# transistor-test-v3.net
KiCad netlist of a schematic drawn in EAGLE
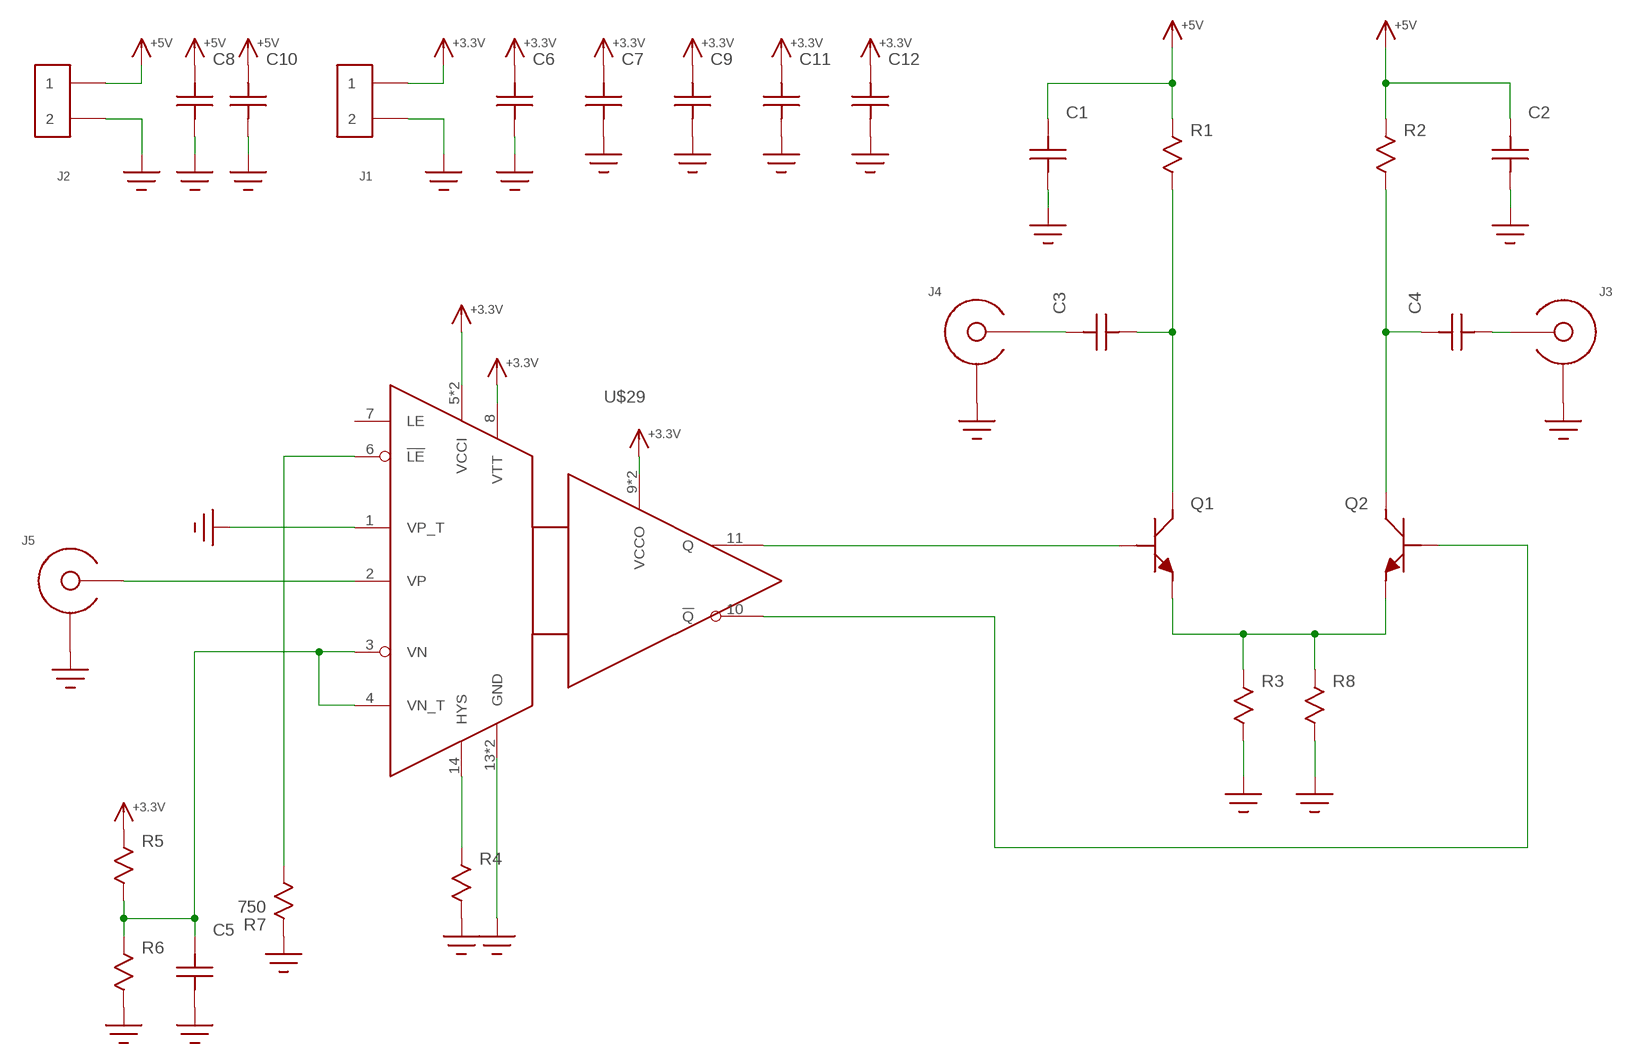
[diagram p0: schematic, sheet 1]

(export (version "E")
  (design (tool "Eeschema 10.0.6"))
  (components
    (comp (ref "C1")
      (value "C0603")
      (footprint "eagle-import:C0603")
      (libsource (lib "eagle-import") (part "C0603"))
    )
    (comp (ref "C2")
      (value "C0603")
      (footprint "eagle-import:C0603")
      (libsource (lib "eagle-import") (part "C0603"))
    )
    (comp (ref "C3")
      (value "C0603")
      (footprint "eagle-import:C0603")
      (libsource (lib "eagle-import") (part "C0603"))
    )
    (comp (ref "C4")
      (value "C0603")
      (footprint "eagle-import:C0603")
      (libsource (lib "eagle-import") (part "C0603"))
    )
    (comp (ref "C5")
      (value "C0603")
      (footprint "eagle-import:C0603")
      (libsource (lib "eagle-import") (part "C0603"))
    )
    (comp (ref "C6")
      (value "C1206")
      (footprint "eagle-import:1206")
      (libsource (lib "eagle-import") (part "C1206"))
    )
    (comp (ref "C7")
      (value "C0603")
      (footprint "eagle-import:C0603")
      (libsource (lib "eagle-import") (part "C0603"))
    )
    (comp (ref "C8")
      (value "C1206")
      (footprint "eagle-import:1206")
      (libsource (lib "eagle-import") (part "C1206"))
    )
    (comp (ref "C9")
      (value "C0603")
      (footprint "eagle-import:C0603")
      (libsource (lib "eagle-import") (part "C0603"))
    )
    (comp (ref "C10")
      (value "C1206")
      (footprint "eagle-import:1206")
      (libsource (lib "eagle-import") (part "C1206"))
    )
    (comp (ref "C11")
      (value "C0603")
      (footprint "eagle-import:C0603")
      (libsource (lib "eagle-import") (part "C0603"))
    )
    (comp (ref "C12")
      (value "C0603")
      (footprint "eagle-import:C0603")
      (libsource (lib "eagle-import") (part "C0603"))
    )
    (comp (ref "J1")
      (value "HEADER_2PIN")
      (footprint "eagle-import:HEADER_2PIN")
      (libsource (lib "eagle-import") (part "HEADER_2PIN"))
    )
    (comp (ref "J2")
      (value "HEADER_2PIN")
      (footprint "eagle-import:HEADER_2PIN")
      (libsource (lib "eagle-import") (part "HEADER_2PIN"))
    )
    (comp (ref "J3")
      (value "SMA-EDGE-LAUNCH4L_4030_TAPER")
      (footprint "eagle-import:SMA_EDGE_LAUNCH_4L_4030_TAPER")
      (libsource (lib "eagle-import") (part "SMA-EDGE-LAUNCH4L_4030_TAPER"))
    )
    (comp (ref "J4")
      (value "SMA-EDGE-LAUNCH4L_4030_TAPER")
      (footprint "eagle-import:SMA_EDGE_LAUNCH_4L_4030_TAPER")
      (libsource (lib "eagle-import") (part "SMA-EDGE-LAUNCH4L_4030_TAPER"))
    )
    (comp (ref "J5")
      (value "SMA-EDGE-LAUNCH4L_4030_TAPER")
      (footprint "eagle-import:SMA_EDGE_LAUNCH_4L_4030_TAPER")
      (libsource (lib "eagle-import") (part "SMA-EDGE-LAUNCH4L_4030_TAPER"))
    )
    (comp (ref "Q1")
      (value "MCH4020")
      (footprint "eagle-import:SOT343")
      (libsource (lib "eagle-import") (part "MCH4020"))
    )
    (comp (ref "Q2")
      (value "MCH4020")
      (footprint "eagle-import:SOT343")
      (libsource (lib "eagle-import") (part "MCH4020"))
    )
    (comp (ref "R1")
      (value "R0603")
      (footprint "eagle-import:R0603")
      (libsource (lib "eagle-import") (part "R0603"))
    )
    (comp (ref "R2")
      (value "R0603")
      (footprint "eagle-import:R0603")
      (libsource (lib "eagle-import") (part "R0603"))
    )
    (comp (ref "R3")
      (value "R0603")
      (footprint "eagle-import:R0603")
      (libsource (lib "eagle-import") (part "R0603"))
    )
    (comp (ref "R4")
      (value "R0603")
      (footprint "eagle-import:R0603")
      (libsource (lib "eagle-import") (part "R0603"))
    )
    (comp (ref "R5")
      (value "R0603")
      (footprint "eagle-import:R0603")
      (libsource (lib "eagle-import") (part "R0603"))
    )
    (comp (ref "R6")
      (value "R0603")
      (footprint "eagle-import:R0603")
      (libsource (lib "eagle-import") (part "R0603"))
    )
    (comp (ref "R7")
      (value "750")
      (footprint "eagle-import:R0603")
      (libsource (lib "eagle-import") (part "R0603"))
    )
    (comp (ref "R8")
      (value "R0603")
      (footprint "eagle-import:R0603")
      (libsource (lib "eagle-import") (part "R0603"))
    )
    (comp (ref "U$29")
      (value "ADCMP572")
      (footprint "eagle-import:TQFN16-EP")
      (libsource (lib "eagle-import") (part "ADCMP572"))
    )
  )
  (nets
    (net (code "1") (name "+3.3V") (class "Default")
      (node (ref "C11") (pin "P$2") (pinfunction "P$2_P$2") (pintype "bidirectional"))
      (node (ref "C12") (pin "P$2") (pinfunction "P$2_P$2") (pintype "bidirectional"))
      (node (ref "C6") (pin "P$2") (pinfunction "P$2_P$2") (pintype "bidirectional"))
      (node (ref "C7") (pin "P$2") (pinfunction "P$2_P$2") (pintype "bidirectional"))
      (node (ref "C9") (pin "P$2") (pinfunction "P$2_P$2") (pintype "bidirectional"))
      (node (ref "J1") (pin "1") (pinfunction "1_1") (pintype "bidirectional"))
      (node (ref "R5") (pin "P$1") (pinfunction "P$3_P$1") (pintype "bidirectional"))
      (node (ref "U$29") (pin "12") (pinfunction "VCCO_12") (pintype "bidirectional"))
      (node (ref "U$29") (pin "16") (pinfunction "VCCI_16") (pintype "bidirectional"))
      (node (ref "U$29") (pin "5") (pinfunction "VCCI_5") (pintype "bidirectional"))
      (node (ref "U$29") (pin "8") (pinfunction "VTT_8") (pintype "bidirectional"))
      (node (ref "U$29") (pin "9") (pinfunction "VCCO_9") (pintype "bidirectional"))
    )
    (net (code "2") (name "+5V") (class "Default")
      (node (ref "C1") (pin "P$2") (pinfunction "P$2_P$2") (pintype "bidirectional"))
      (node (ref "C10") (pin "P$2") (pinfunction "P$2_P$2") (pintype "bidirectional"))
      (node (ref "C2") (pin "P$2") (pinfunction "P$2_P$2") (pintype "bidirectional"))
      (node (ref "C8") (pin "P$2") (pinfunction "P$2_P$2") (pintype "bidirectional"))
      (node (ref "J2") (pin "1") (pinfunction "1_1") (pintype "bidirectional"))
      (node (ref "R1") (pin "P$1") (pinfunction "P$3_P$1") (pintype "bidirectional"))
      (node (ref "R2") (pin "P$1") (pinfunction "P$3_P$1") (pintype "bidirectional"))
    )
    (net (code "3") (name "GND") (class "Default")
      (node (ref "C1") (pin "P$1") (pinfunction "P$1_P$1") (pintype "bidirectional"))
      (node (ref "C10") (pin "P$1") (pinfunction "P$1_P$1") (pintype "bidirectional"))
      (node (ref "C11") (pin "P$1") (pinfunction "P$1_P$1") (pintype "bidirectional"))
      (node (ref "C12") (pin "P$1") (pinfunction "P$1_P$1") (pintype "bidirectional"))
      (node (ref "C2") (pin "P$1") (pinfunction "P$1_P$1") (pintype "bidirectional"))
      (node (ref "C5") (pin "P$1") (pinfunction "P$1_P$1") (pintype "bidirectional"))
      (node (ref "C6") (pin "P$1") (pinfunction "P$1_P$1") (pintype "bidirectional"))
      (node (ref "C7") (pin "P$1") (pinfunction "P$1_P$1") (pintype "bidirectional"))
      (node (ref "C8") (pin "P$1") (pinfunction "P$1_P$1") (pintype "bidirectional"))
      (node (ref "C9") (pin "P$1") (pinfunction "P$1_P$1") (pintype "bidirectional"))
      (node (ref "J1") (pin "2") (pinfunction "2_2") (pintype "bidirectional"))
      (node (ref "J2") (pin "2") (pinfunction "2_2") (pintype "bidirectional"))
      (node (ref "J3") (pin "BOTTOM_GND") (pinfunction "SHIELD_BOTTOM_GND") (pintype "bidirectional"))
      (node (ref "J3") (pin "GND@1") (pinfunction "SHIELD_GND@1") (pintype "bidirectional"))
      (node (ref "J3") (pin "GND@14") (pinfunction "SHIELD_GND@14") (pintype "bidirectional"))
      (node (ref "J3") (pin "GND@15") (pinfunction "SHIELD_GND@15") (pintype "bidirectional"))
      (node (ref "J3") (pin "GND@16") (pinfunction "SHIELD_GND@16") (pintype "bidirectional"))
      (node (ref "J3") (pin "GND@17") (pinfunction "SHIELD_GND@17") (pintype "bidirectional"))
      (node (ref "J3") (pin "GND@2") (pinfunction "SHIELD_GND@2") (pintype "bidirectional"))
      (node (ref "J3") (pin "GND@3") (pinfunction "SHIELD_GND@3") (pintype "bidirectional"))
      (node (ref "J3") (pin "GND@4") (pinfunction "SHIELD_GND@4") (pintype "bidirectional"))
      (node (ref "J3") (pin "GND@5") (pinfunction "SHIELD_GND@5") (pintype "bidirectional"))
      (node (ref "J3") (pin "GND@6") (pinfunction "SHIELD_GND@6") (pintype "bidirectional"))
      (node (ref "J3") (pin "GND@7") (pinfunction "SHIELD_GND@7") (pintype "bidirectional"))
      (node (ref "J3") (pin "GND@8") (pinfunction "SHIELD_GND@8") (pintype "bidirectional"))
      (node (ref "J3") (pin "GND_PAD1") (pinfunction "SHIELD_GND_PAD1") (pintype "bidirectional"))
      (node (ref "J3") (pin "GND_PAD2") (pinfunction "SHIELD_GND_PAD2") (pintype "bidirectional"))
      (node (ref "J3") (pin "P$1") (pinfunction "SHIELD_P$1") (pintype "bidirectional"))
      (node (ref "J3") (pin "P$2") (pinfunction "SHIELD_P$2") (pintype "bidirectional"))
      (node (ref "J4") (pin "BOTTOM_GND") (pinfunction "SHIELD_BOTTOM_GND") (pintype "bidirectional"))
      (node (ref "J4") (pin "GND@1") (pinfunction "SHIELD_GND@1") (pintype "bidirectional"))
      (node (ref "J4") (pin "GND@14") (pinfunction "SHIELD_GND@14") (pintype "bidirectional"))
      (node (ref "J4") (pin "GND@15") (pinfunction "SHIELD_GND@15") (pintype "bidirectional"))
      (node (ref "J4") (pin "GND@16") (pinfunction "SHIELD_GND@16") (pintype "bidirectional"))
      (node (ref "J4") (pin "GND@17") (pinfunction "SHIELD_GND@17") (pintype "bidirectional"))
      (node (ref "J4") (pin "GND@2") (pinfunction "SHIELD_GND@2") (pintype "bidirectional"))
      (node (ref "J4") (pin "GND@3") (pinfunction "SHIELD_GND@3") (pintype "bidirectional"))
      (node (ref "J4") (pin "GND@4") (pinfunction "SHIELD_GND@4") (pintype "bidirectional"))
      (node (ref "J4") (pin "GND@5") (pinfunction "SHIELD_GND@5") (pintype "bidirectional"))
      (node (ref "J4") (pin "GND@6") (pinfunction "SHIELD_GND@6") (pintype "bidirectional"))
      (node (ref "J4") (pin "GND@7") (pinfunction "SHIELD_GND@7") (pintype "bidirectional"))
      (node (ref "J4") (pin "GND@8") (pinfunction "SHIELD_GND@8") (pintype "bidirectional"))
      (node (ref "J4") (pin "GND_PAD1") (pinfunction "SHIELD_GND_PAD1") (pintype "bidirectional"))
      (node (ref "J4") (pin "GND_PAD2") (pinfunction "SHIELD_GND_PAD2") (pintype "bidirectional"))
      (node (ref "J4") (pin "P$1") (pinfunction "SHIELD_P$1") (pintype "bidirectional"))
      (node (ref "J4") (pin "P$2") (pinfunction "SHIELD_P$2") (pintype "bidirectional"))
      (node (ref "J5") (pin "BOTTOM_GND") (pinfunction "SHIELD_BOTTOM_GND") (pintype "bidirectional"))
      (node (ref "J5") (pin "GND@1") (pinfunction "SHIELD_GND@1") (pintype "bidirectional"))
      (node (ref "J5") (pin "GND@14") (pinfunction "SHIELD_GND@14") (pintype "bidirectional"))
      (node (ref "J5") (pin "GND@15") (pinfunction "SHIELD_GND@15") (pintype "bidirectional"))
      (node (ref "J5") (pin "GND@16") (pinfunction "SHIELD_GND@16") (pintype "bidirectional"))
      (node (ref "J5") (pin "GND@17") (pinfunction "SHIELD_GND@17") (pintype "bidirectional"))
      (node (ref "J5") (pin "GND@2") (pinfunction "SHIELD_GND@2") (pintype "bidirectional"))
      (node (ref "J5") (pin "GND@3") (pinfunction "SHIELD_GND@3") (pintype "bidirectional"))
      (node (ref "J5") (pin "GND@4") (pinfunction "SHIELD_GND@4") (pintype "bidirectional"))
      (node (ref "J5") (pin "GND@5") (pinfunction "SHIELD_GND@5") (pintype "bidirectional"))
      (node (ref "J5") (pin "GND@6") (pinfunction "SHIELD_GND@6") (pintype "bidirectional"))
      (node (ref "J5") (pin "GND@7") (pinfunction "SHIELD_GND@7") (pintype "bidirectional"))
      (node (ref "J5") (pin "GND@8") (pinfunction "SHIELD_GND@8") (pintype "bidirectional"))
      (node (ref "J5") (pin "GND_PAD1") (pinfunction "SHIELD_GND_PAD1") (pintype "bidirectional"))
      (node (ref "J5") (pin "GND_PAD2") (pinfunction "SHIELD_GND_PAD2") (pintype "bidirectional"))
      (node (ref "J5") (pin "P$1") (pinfunction "SHIELD_P$1") (pintype "bidirectional"))
      (node (ref "J5") (pin "P$2") (pinfunction "SHIELD_P$2") (pintype "bidirectional"))
      (node (ref "R3") (pin "P$2") (pinfunction "P$4_P$2") (pintype "bidirectional"))
      (node (ref "R4") (pin "P$2") (pinfunction "P$4_P$2") (pintype "bidirectional"))
      (node (ref "R6") (pin "P$2") (pinfunction "P$4_P$2") (pintype "bidirectional"))
      (node (ref "R7") (pin "P$1") (pinfunction "P$3_P$1") (pintype "bidirectional"))
      (node (ref "R8") (pin "P$2") (pinfunction "P$4_P$2") (pintype "bidirectional"))
      (node (ref "U$29") (pin "1") (pinfunction "VP_T_1") (pintype "bidirectional"))
      (node (ref "U$29") (pin "13") (pinfunction "GND_13") (pintype "bidirectional"))
      (node (ref "U$29") (pin "15") (pinfunction "GND_15") (pintype "bidirectional"))
    )
    (net (code "4") (name "Net-(J3-CENTER)") (class "Default")
      (node (ref "C4") (pin "P$1") (pinfunction "P$1_P$1") (pintype "bidirectional"))
      (node (ref "J3") (pin "CENTER@1") (pinfunction "CENTER_CENTER@1") (pintype "bidirectional"))
    )
    (net (code "5") (name "Net-(J4-CENTER)") (class "Default")
      (node (ref "C3") (pin "P$2") (pinfunction "P$2_P$2") (pintype "bidirectional"))
      (node (ref "J4") (pin "CENTER@1") (pinfunction "CENTER_CENTER@1") (pintype "bidirectional"))
    )
    (net (code "6") (name "Net-(J5-CENTER)") (class "Default")
      (node (ref "J5") (pin "CENTER@1") (pinfunction "CENTER_CENTER@1") (pintype "bidirectional"))
      (node (ref "U$29") (pin "2") (pinfunction "VP_2") (pintype "bidirectional"))
    )
    (net (code "7") (name "Net-(Q1-B)") (class "Default")
      (node (ref "Q1") (pin "3") (pinfunction "B_3") (pintype "bidirectional"))
      (node (ref "U$29") (pin "11") (pinfunction "Q_11") (pintype "bidirectional"))
    )
    (net (code "8") (name "Net-(Q1-C)") (class "Default")
      (node (ref "C3") (pin "P$1") (pinfunction "P$1_P$1") (pintype "bidirectional"))
      (node (ref "Q1") (pin "1") (pinfunction "C_1") (pintype "bidirectional"))
      (node (ref "R1") (pin "P$2") (pinfunction "P$4_P$2") (pintype "bidirectional"))
    )
    (net (code "9") (name "Net-(Q2-B)") (class "Default")
      (node (ref "Q2") (pin "3") (pinfunction "B_3") (pintype "bidirectional"))
      (node (ref "U$29") (pin "10") (pinfunction "~{Q}_10") (pintype "bidirectional"))
    )
    (net (code "10") (name "Net-(Q2-C)") (class "Default")
      (node (ref "C4") (pin "P$2") (pinfunction "P$2_P$2") (pintype "bidirectional"))
      (node (ref "Q2") (pin "1") (pinfunction "C_1") (pintype "bidirectional"))
      (node (ref "R2") (pin "P$2") (pinfunction "P$4_P$2") (pintype "bidirectional"))
    )
    (net (code "11") (name "Net-(R3-P$3)") (class "Default")
      (node (ref "Q1") (pin "2") (pinfunction "E_2") (pintype "bidirectional"))
      (node (ref "Q1") (pin "4") (pinfunction "E_4") (pintype "bidirectional"))
      (node (ref "Q2") (pin "2") (pinfunction "E_2") (pintype "bidirectional"))
      (node (ref "Q2") (pin "4") (pinfunction "E_4") (pintype "bidirectional"))
      (node (ref "R3") (pin "P$1") (pinfunction "P$3_P$1") (pintype "bidirectional"))
      (node (ref "R8") (pin "P$1") (pinfunction "P$3_P$1") (pintype "bidirectional"))
    )
    (net (code "12") (name "Net-(R4-P$3)") (class "Default")
      (node (ref "R4") (pin "P$1") (pinfunction "P$3_P$1") (pintype "bidirectional"))
      (node (ref "U$29") (pin "14") (pinfunction "HYS_14") (pintype "bidirectional"))
    )
    (net (code "13") (name "Net-(R5-P$4)") (class "Default")
      (node (ref "C5") (pin "P$2") (pinfunction "P$2_P$2") (pintype "bidirectional"))
      (node (ref "R5") (pin "P$2") (pinfunction "P$4_P$2") (pintype "bidirectional"))
      (node (ref "R6") (pin "P$1") (pinfunction "P$3_P$1") (pintype "bidirectional"))
      (node (ref "U$29") (pin "3") (pinfunction "VN_3") (pintype "bidirectional"))
      (node (ref "U$29") (pin "4") (pinfunction "VN_T_4") (pintype "bidirectional"))
    )
    (net (code "14") (name "Net-(R7-P$4)") (class "Default")
      (node (ref "R7") (pin "P$2") (pinfunction "P$4_P$2") (pintype "bidirectional"))
      (node (ref "U$29") (pin "6") (pinfunction "~{LE}_6") (pintype "bidirectional"))
    )
    (net (code "15") (name "unconnected-(U$29-LE-Pad7)") (class "Default")
      (node (ref "U$29") (pin "7") (pinfunction "LE_7") (pintype "bidirectional"))
    )
  )
)
